# Bee_Hive_MainBoard_V3.net
KiCad netlist of a schematic drawn in Altium Designer
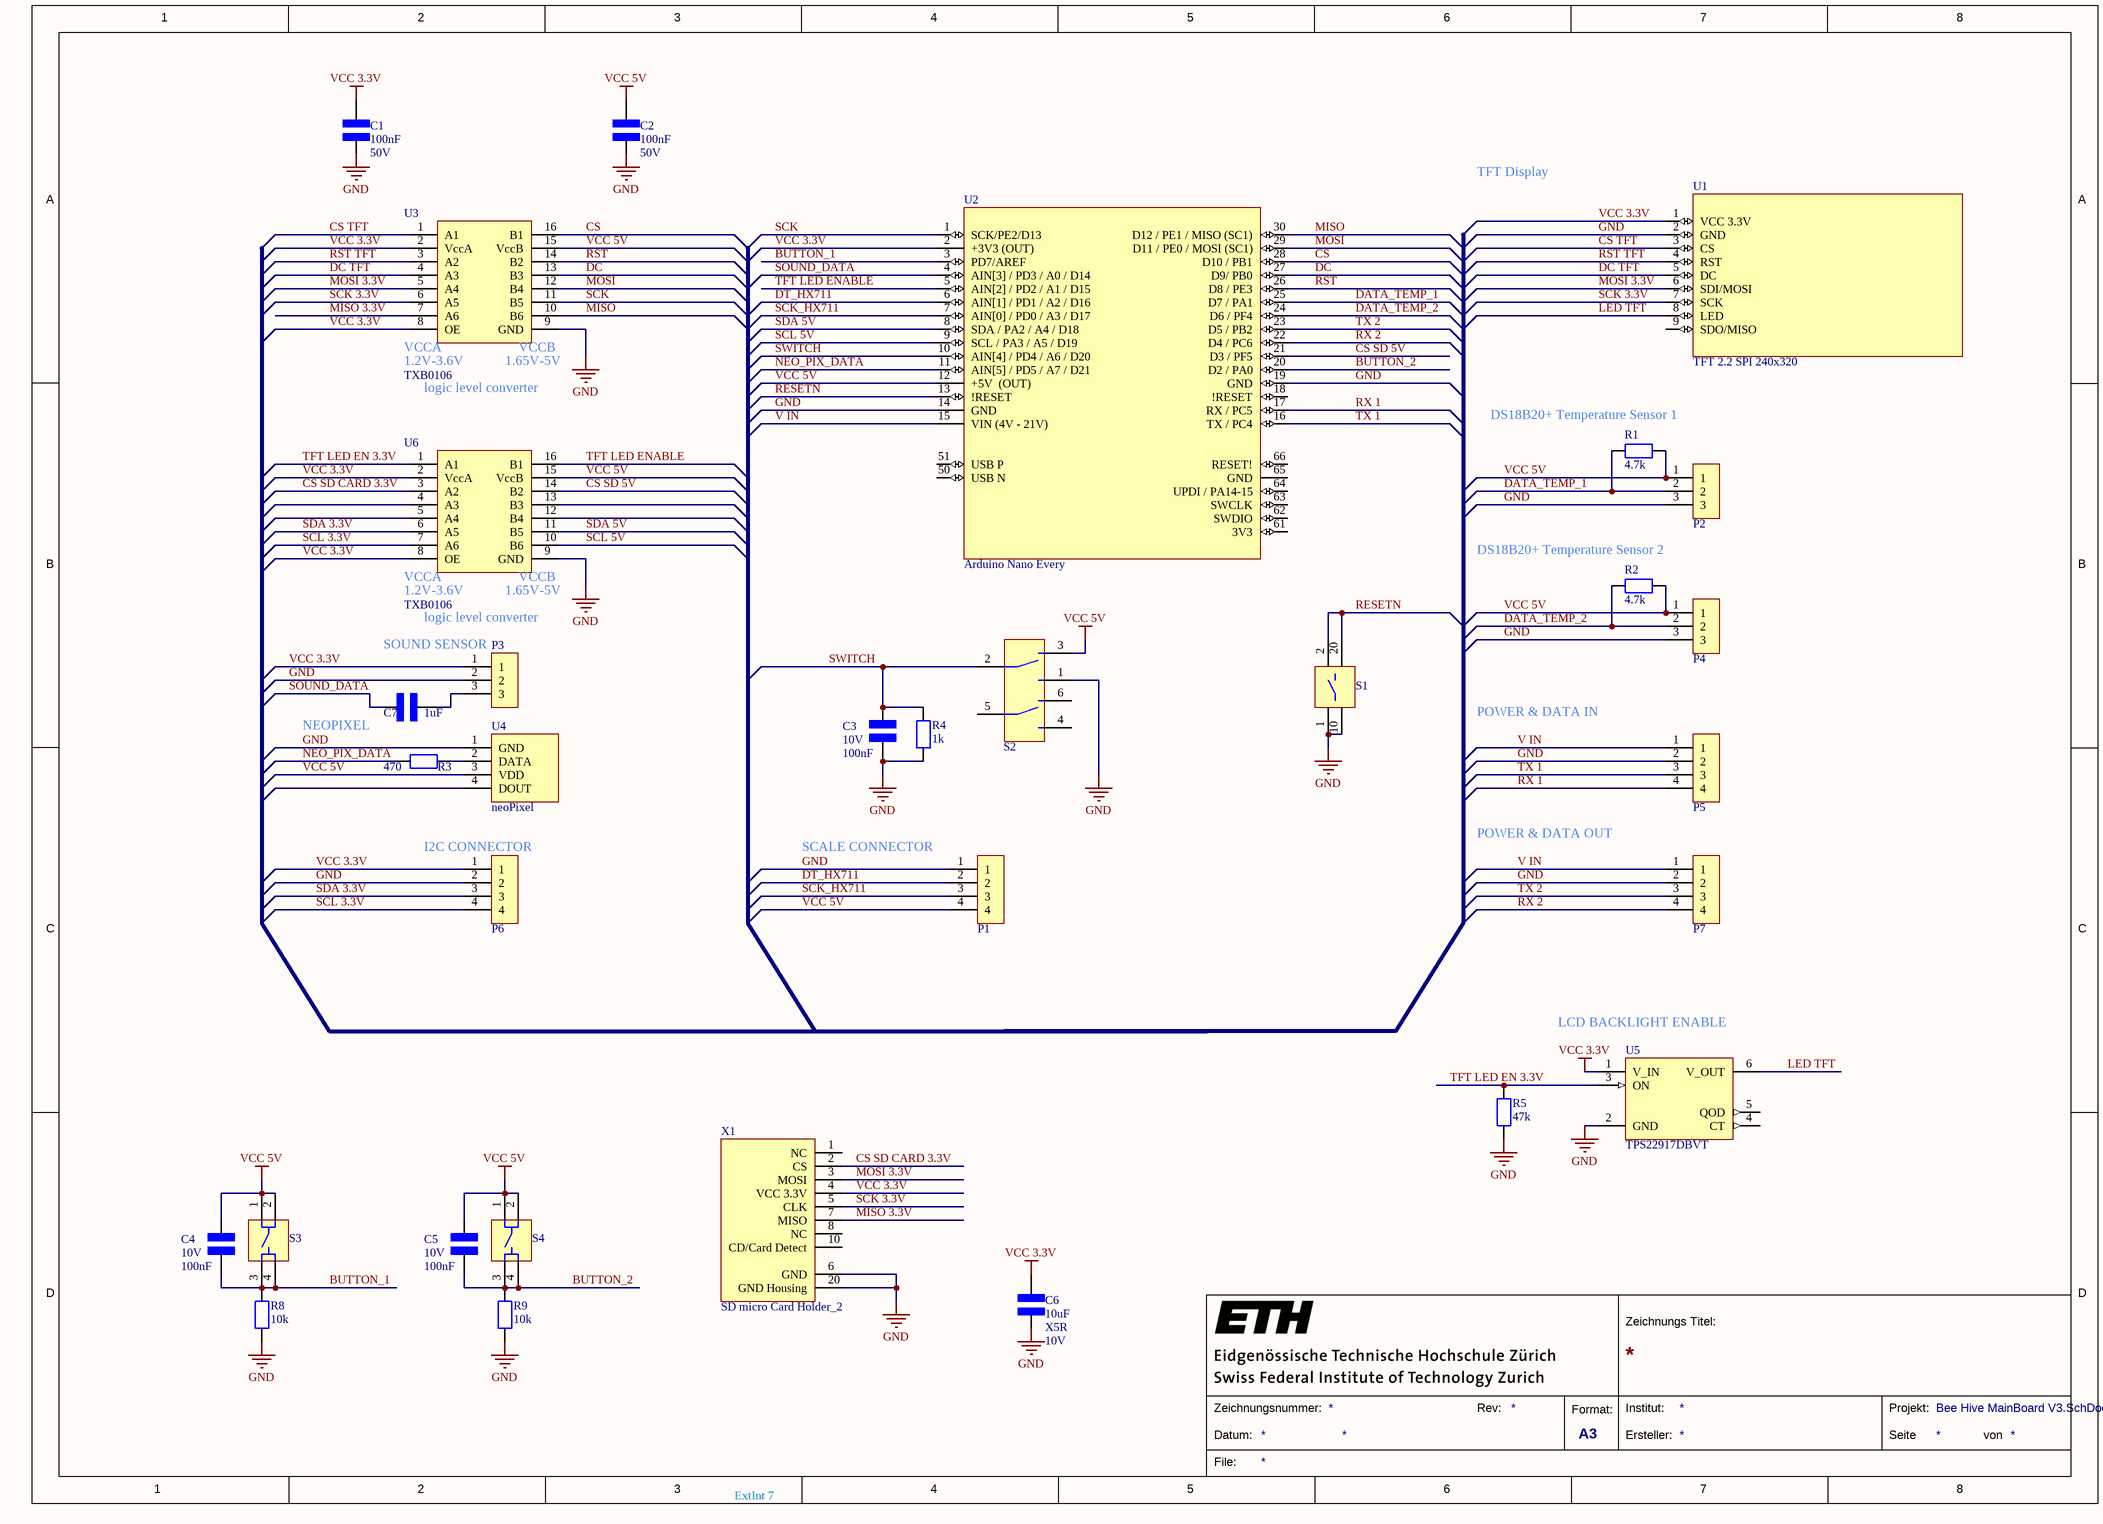
[diagram p0: Bee Hive MainBoard V3.SchDoc]

(export (version "E")
  (design (tool "Eeschema 10.0.6"))
  (components
    (comp (ref "C1")
      (value "100nF")
      (footprint "CAP 0603")
      (description "C CERAMIC SMD")
      (fields (field (name "UMAX") "50V") (field (name "Comment") "100nF 0603_1"))
      (libsource (lib "Library CAP") (part "100nF 0603_1"))
    )
    (comp (ref "C2")
      (value "100nF")
      (footprint "CAP 0603")
      (description "C CERAMIC SMD")
      (fields (field (name "UMAX") "50V") (field (name "Comment") "100nF 0603_1"))
      (libsource (lib "Library CAP") (part "100nF 0603_1"))
    )
    (comp (ref "C3")
      (value "100nF")
      (footprint "CAP 0603")
      (description "C CERAMIC SMD")
      (fields (field (name "UMAX") "10V") (field (name "Comment") "100nF 0603"))
      (libsource (lib "Library CAP") (part "100nF 0603"))
    )
    (comp (ref "C4")
      (value "100nF")
      (footprint "CAP 0603")
      (description "C CERAMIC SMD")
      (fields (field (name "UMAX") "10V") (field (name "Comment") "100nF 0603"))
      (libsource (lib "Library CAP") (part "100nF 0603"))
    )
    (comp (ref "C5")
      (value "100nF")
      (footprint "CAP 0603")
      (description "C CERAMIC SMD")
      (fields (field (name "UMAX") "10V") (field (name "Comment") "100nF 0603"))
      (libsource (lib "Library CAP") (part "100nF 0603"))
    )
    (comp (ref "C6")
      (value "10uF")
      (footprint "CAP 0603")
      (description "C CERAMIC SMD")
      (fields
        (field (name "DIELEKTRIKUM") "X5R")
        (field (name "UMAX") "10V")
        (field (name "Comment") "10uF 0603")
      )
      (libsource (lib "Library CAP") (part "10uF 0603"))
    )
    (comp (ref "C7")
      (value "1uF")
      (footprint "CAP 0805")
      (description "C CERAMIC SMD")
      (fields (field (name "Comment") "100nF 0805"))
      (libsource (lib "Library CAP") (part "100nF 0805"))
    )
    (comp (ref "P1")
      (value "4-Pin Right Angle Housing")
      (footprint "4PIN - RND 205-EK254-2.54-04P")
      (description "4-Pin")
      (libsource (lib "Library Scematic") (part "4-Pin Screw Terminal"))
    )
    (comp (ref "P2")
      (value "3-Pin Right Angle Housing")
      (footprint "3PIN - RND 205-EK254-2.54-03P")
      (description "3-Pin")
      (libsource (lib "Library Scematic") (part "3-Pin Screw Terminal"))
    )
    (comp (ref "P3")
      (value "3-Pin Right Angle Housing")
      (footprint "3PIN - RND 205-EK254-2.54-03P")
      (description "3-Pin")
      (libsource (lib "Library Scematic") (part "3-Pin Screw Terminal"))
    )
    (comp (ref "P4")
      (value "3-Pin Right Angle Housing")
      (footprint "3PIN - RND 205-EK254-2.54-03P")
      (description "3-Pin")
      (libsource (lib "Library Scematic") (part "3-Pin Screw Terminal"))
    )
    (comp (ref "P5")
      (value "4-Pin Right Angle Housing")
      (footprint "4PIN - RND 205-EK254-2.54-04P")
      (description "4-Pin")
      (libsource (lib "Library Scematic") (part "4-Pin Screw Terminal"))
    )
    (comp (ref "P6")
      (value "4-Pin Right Angle Housing")
      (footprint "4PIN - RND 205-EK254-2.54-04P")
      (description "4-Pin")
      (libsource (lib "Library Scematic") (part "4-Pin Screw Terminal"))
    )
    (comp (ref "P7")
      (value "4-Pin Right Angle Housing")
      (footprint "4PIN - RND 205-EK254-2.54-04P")
      (description "4-Pin")
      (libsource (lib "Library Scematic") (part "4-Pin Screw Terminal"))
    )
    (comp (ref "R1")
      (value "4.7k")
      (footprint "RES 0603 FOOTPRINT")
      (description "R SMD")
      (fields (field (name "Comment") "4.7k Ohm 0603"))
      (libsource (lib "Library RES") (part "4.7k Ohm 0603"))
    )
    (comp (ref "R2")
      (value "4.7k")
      (footprint "RES 0603 FOOTPRINT")
      (description "R SMD")
      (fields (field (name "Comment") "4.7k Ohm 0603"))
      (libsource (lib "Library RES") (part "4.7k Ohm 0603"))
    )
    (comp (ref "R3")
      (value "470")
      (footprint "RES 0603 FOOTPRINT")
      (description "R SMD")
      (fields (field (name "Comment") "470 Ohm 0603"))
      (libsource (lib "Library RES") (part "470 Ohm 0603"))
    )
    (comp (ref "R4")
      (value "1k")
      (footprint "RES 0603 FOOTPRINT")
      (description "R SMD")
      (fields (field (name "Comment") "1k Ohm 0603"))
      (libsource (lib "Library RES") (part "1k Ohm 0603"))
    )
    (comp (ref "R5")
      (value "47k")
      (footprint "RES 0603 FOOTPRINT")
      (description "R SMD")
      (fields (field (name "Comment") "47k Ohm 0603"))
      (libsource (lib "Library RES") (part "47k Ohm 0603"))
    )
    (comp (ref "R8")
      (value "10k")
      (footprint "RES 0603 FOOTPRINT")
      (description "R SMD")
      (fields (field (name "Comment") "10k Ohm 0603"))
      (libsource (lib "Library RES") (part "10k Ohm 0603"))
    )
    (comp (ref "R9")
      (value "10k")
      (footprint "RES 0603 FOOTPRINT")
      (description "R SMD")
      (fields (field (name "Comment") "10k Ohm 0603"))
      (libsource (lib "Library RES") (part "10k Ohm 0603"))
    )
    (comp (ref "S1")
      (value "Taster Print_SMD_2")
      (footprint "Taster Print - SMD - KMR241G LFS")
      (description "Taster")
      (libsource (lib "Library Scematic") (part "Taster Print_SMD_2"))
    )
    (comp (ref "S2")
      (value "Schiebeschalter EG2207")
      (footprint "Schiebeschalter on-on 2 P, EG2207")
      (description "Schiebeschalter on-on PCM12SMTR")
      (libsource (lib "Library Scematic") (part "Schiebeschalter EG2207"))
    )
    (comp (ref "S3")
      (value "Taster Print_SMD_3")
      (footprint "Taster Print - SMD - PTS647SM70SMTR2LFS")
      (description "Taster")
      (libsource (lib "Library Scematic") (part "Taster Print_SMD_6"))
    )
    (comp (ref "S4")
      (value "Taster Print_SMD_3")
      (footprint "Taster Print - SMD - PTS647SM70SMTR2LFS")
      (description "Taster")
      (libsource (lib "Library Scematic") (part "Taster Print_SMD_6"))
    )
    (comp (ref "U1")
      (value "TFT 2.2 SPI 240x320")
      (footprint "TFT 2.2 SPI 240x320")
      (libsource (lib "Library Scematic") (part "TFT 2.2 SPI 240x320"))
    )
    (comp (ref "U2")
      (value "Arduino Nano Every")
      (footprint "Arduino Nano Every")
      (description "https://store.arduino.cc/nano-every-pack")
      (libsource (lib "Library Scematic") (part "Arduino Nano Every"))
    )
    (comp (ref "U3")
      (value "TXB0106")
      (footprint "TSSOP-16L")
      (description "Level Converter TXB0106")
      (libsource (lib "Library Scematic") (part "TXB0106 Level Converter"))
    )
    (comp (ref "U4")
      (value "neoPixel")
      (footprint "neoPixel 5050 adafruit 1655")
      (description "neoPixel 5050 adafruit 1655")
      (libsource (lib "Library Scematic") (part "neoPixel 5050 adafruit 1655"))
    )
    (comp (ref "U5")
      (value "TPS22917DBVT")
      (footprint "SOT23 - 6")
      (description "High Side Switch")
      (libsource (lib "Library Scematic") (part "TPS22917DBVT"))
    )
    (comp (ref "U6")
      (value "TXB0106")
      (footprint "TSSOP-16L")
      (description "Level Converter TXB0106")
      (libsource (lib "Library Scematic") (part "TXB0106 Level Converter"))
    )
    (comp (ref "X1")
      (value "SD micro Card Holder_2")
      (footprint "SD Card Holder - micro - 2 - sd Card inserted")
      (description "SD micro Card  Holder")
      (libsource (lib "Library Scematic") (part "SD micro Card Holder_2"))
    )
  )
  (nets
    (net (code "1") (name "/BUTTON_1") (class "Default")
      (node (ref "C4") (pin "2") (pinfunction "2_2") (pintype "passive"))
      (node (ref "R8") (pin "2") (pinfunction "2_2") (pintype "passive"))
      (node (ref "S3") (pin "3") (pinfunction "3_3") (pintype "passive"))
      (node (ref "S3") (pin "4") (pinfunction "4_4") (pintype "passive"))
      (node (ref "U2") (pin "3") (pinfunction "PD7/AREF_3") (pintype "bidirectional"))
    )
    (net (code "2") (name "/BUTTON_2") (class "Default")
      (node (ref "C5") (pin "2") (pinfunction "2_2") (pintype "passive"))
      (node (ref "R9") (pin "2") (pinfunction "2_2") (pintype "passive"))
      (node (ref "S4") (pin "3") (pinfunction "3_3") (pintype "passive"))
      (node (ref "S4") (pin "4") (pinfunction "4_4") (pintype "passive"))
      (node (ref "U2") (pin "20") (pinfunction "D2_/_PA0_20") (pintype "bidirectional"))
    )
    (net (code "3") (name "/CS") (class "Default")
      (node (ref "U2") (pin "28") (pinfunction "D10_/_PB1_28") (pintype "bidirectional"))
      (node (ref "U3") (pin "16") (pinfunction "B1_16") (pintype "passive"))
    )
    (net (code "4") (name "/CS SD 5V") (class "Default")
      (node (ref "U2") (pin "21") (pinfunction "D3_/_PF5_21") (pintype "bidirectional"))
      (node (ref "U6") (pin "14") (pinfunction "B2_14") (pintype "passive"))
    )
    (net (code "5") (name "/CS SD CARD 3.3V") (class "Default")
      (node (ref "U6") (pin "3") (pinfunction "A2_3") (pintype "passive"))
      (node (ref "X1") (pin "2") (pinfunction "CS_2") (pintype "passive"))
    )
    (net (code "6") (name "/CS TFT") (class "Default")
      (node (ref "U1") (pin "3") (pinfunction "CS_3") (pintype "bidirectional"))
      (node (ref "U3") (pin "1") (pinfunction "A1_1") (pintype "power_in"))
    )
    (net (code "7") (name "/DATA_TEMP_1") (class "Default")
      (node (ref "P2") (pin "2") (pinfunction "2_2") (pintype "passive"))
      (node (ref "R1") (pin "2") (pinfunction "2_2") (pintype "passive"))
      (node (ref "U2") (pin "25") (pinfunction "D7_/_PA1_25") (pintype "bidirectional"))
    )
    (net (code "8") (name "/DATA_TEMP_2") (class "Default")
      (node (ref "P4") (pin "2") (pinfunction "2_2") (pintype "passive"))
      (node (ref "R2") (pin "2") (pinfunction "2_2") (pintype "passive"))
      (node (ref "U2") (pin "24") (pinfunction "D6_/_PF4_24") (pintype "bidirectional"))
    )
    (net (code "9") (name "/DC") (class "Default")
      (node (ref "U2") (pin "27") (pinfunction "D9/_PB0_27") (pintype "bidirectional"))
      (node (ref "U3") (pin "13") (pinfunction "B3_13") (pintype "passive"))
    )
    (net (code "10") (name "/DC TFT") (class "Default")
      (node (ref "U1") (pin "5") (pinfunction "DC_5") (pintype "bidirectional"))
      (node (ref "U3") (pin "4") (pinfunction "A3_4") (pintype "passive"))
    )
    (net (code "11") (name "/DT_HX711") (class "Default")
      (node (ref "P1") (pin "2") (pinfunction "2_2") (pintype "passive"))
      (node (ref "U2") (pin "6") (pinfunction "AIN[1]_/_PD1_/_A2_/_D16_6") (pintype "bidirectional"))
    )
    (net (code "12") (name "/LED TFT") (class "Default")
      (node (ref "U1") (pin "8") (pinfunction "LED_8") (pintype "bidirectional"))
      (node (ref "U5") (pin "6") (pinfunction "V_OUT_6") (pintype "power_in"))
    )
    (net (code "13") (name "/MISO") (class "Default")
      (node (ref "U2") (pin "30") (pinfunction "D12_/_PE1_/_MISO_(SC1)_30") (pintype "bidirectional"))
      (node (ref "U3") (pin "10") (pinfunction "B6_10") (pintype "passive"))
    )
    (net (code "14") (name "/MISO 3.3V") (class "Default")
      (node (ref "U3") (pin "7") (pinfunction "A6_7") (pintype "passive"))
      (node (ref "X1") (pin "7") (pinfunction "MISO_7") (pintype "passive"))
    )
    (net (code "15") (name "/MOSI") (class "Default")
      (node (ref "U2") (pin "29") (pinfunction "D11_/_PE0_/_MOSI_(SC1)_29") (pintype "bidirectional"))
      (node (ref "U3") (pin "12") (pinfunction "B4_12") (pintype "passive"))
    )
    (net (code "16") (name "/MOSI 3.3V") (class "Default")
      (node (ref "U1") (pin "6") (pinfunction "SDI/MOSI_6") (pintype "bidirectional"))
      (node (ref "U3") (pin "5") (pinfunction "A4_5") (pintype "passive"))
      (node (ref "X1") (pin "3") (pinfunction "MOSI_3") (pintype "passive"))
    )
    (net (code "17") (name "/NEO_PIX_DATA") (class "Default")
      (node (ref "R3") (pin "1") (pinfunction "1_1") (pintype "passive"))
      (node (ref "U2") (pin "11") (pinfunction "AIN[5]_/_PD5_/_A7_/_D21_11") (pintype "bidirectional"))
    )
    (net (code "18") (name "/RESETN") (class "Default")
      (node (ref "S1") (pin "2") (pinfunction "2_2") (pintype "passive"))
      (node (ref "S1") (pin "20") (pinfunction "20_20") (pintype "passive"))
      (node (ref "U2") (pin "13") (pinfunction "!RESET_13") (pintype "bidirectional"))
    )
    (net (code "19") (name "/RST") (class "Default")
      (node (ref "U2") (pin "26") (pinfunction "D8_/_PE3_26") (pintype "bidirectional"))
      (node (ref "U3") (pin "14") (pinfunction "B2_14") (pintype "passive"))
    )
    (net (code "20") (name "/RST TFT") (class "Default")
      (node (ref "U1") (pin "4") (pinfunction "RST_4") (pintype "bidirectional"))
      (node (ref "U3") (pin "3") (pinfunction "A2_3") (pintype "passive"))
    )
    (net (code "21") (name "/RX 1") (class "Default")
      (node (ref "P5") (pin "4") (pinfunction "4_4") (pintype "passive"))
      (node (ref "U2") (pin "17") (pinfunction "RX_/_PC5_17") (pintype "bidirectional"))
    )
    (net (code "22") (name "/RX 2") (class "Default")
      (node (ref "P7") (pin "4") (pinfunction "4_4") (pintype "passive"))
      (node (ref "U2") (pin "22") (pinfunction "D4_/_PC6_22") (pintype "bidirectional"))
    )
    (net (code "23") (name "/SCK") (class "Default")
      (node (ref "U2") (pin "1") (pinfunction "SCK/PE2/D13_1") (pintype "bidirectional"))
      (node (ref "U3") (pin "11") (pinfunction "B5_11") (pintype "passive"))
    )
    (net (code "24") (name "/SCK 3.3V") (class "Default")
      (node (ref "U1") (pin "7") (pinfunction "SCK_7") (pintype "bidirectional"))
      (node (ref "U3") (pin "6") (pinfunction "A5_6") (pintype "passive"))
      (node (ref "X1") (pin "5") (pinfunction "CLK_5") (pintype "passive"))
    )
    (net (code "25") (name "/SCK_HX711") (class "Default")
      (node (ref "P1") (pin "3") (pinfunction "3_3") (pintype "passive"))
      (node (ref "U2") (pin "7") (pinfunction "AIN[0]_/_PD0_/_A3_/_D17_7") (pintype "bidirectional"))
    )
    (net (code "26") (name "/SCL 3.3V") (class "Default")
      (node (ref "P6") (pin "4") (pinfunction "4_4") (pintype "passive"))
      (node (ref "U6") (pin "7") (pinfunction "A6_7") (pintype "passive"))
    )
    (net (code "27") (name "/SCL 5V") (class "Default")
      (node (ref "U2") (pin "9") (pinfunction "SCL_/_PA3_/_A5_/_D19_9") (pintype "bidirectional"))
      (node (ref "U6") (pin "10") (pinfunction "B6_10") (pintype "passive"))
    )
    (net (code "28") (name "/SDA 3.3V") (class "Default")
      (node (ref "P6") (pin "3") (pinfunction "3_3") (pintype "passive"))
      (node (ref "U6") (pin "6") (pinfunction "A5_6") (pintype "passive"))
    )
    (net (code "29") (name "/SDA 5V") (class "Default")
      (node (ref "U2") (pin "8") (pinfunction "SDA_/_PA2_/_A4_/_D18_8") (pintype "bidirectional"))
      (node (ref "U6") (pin "11") (pinfunction "B5_11") (pintype "passive"))
    )
    (net (code "30") (name "/SOUND_DATA") (class "Default")
      (node (ref "C7") (pin "1") (pinfunction "1_1") (pintype "passive"))
      (node (ref "U2") (pin "4") (pinfunction "AIN[3]_/_PD3_/_A0_/_D14_4") (pintype "bidirectional"))
    )
    (net (code "31") (name "/SWITCH") (class "Default")
      (node (ref "C3") (pin "1") (pinfunction "1_1") (pintype "passive"))
      (node (ref "R4") (pin "2") (pinfunction "2_2") (pintype "passive"))
      (node (ref "S2") (pin "2") (pinfunction "2_2") (pintype "passive"))
      (node (ref "U2") (pin "10") (pinfunction "AIN[4]_/_PD4_/_A6_/_D20_10") (pintype "bidirectional"))
    )
    (net (code "32") (name "/TFT LED EN 3.3V") (class "Default")
      (node (ref "R5") (pin "2") (pinfunction "2_2") (pintype "passive"))
      (node (ref "U5") (pin "3") (pinfunction "ON_3") (pintype "input"))
      (node (ref "U6") (pin "1") (pinfunction "A1_1") (pintype "power_in"))
    )
    (net (code "33") (name "/TFT LED ENABLE") (class "Default")
      (node (ref "U2") (pin "5") (pinfunction "AIN[2]_/_PD2_/_A1_/_D15_5") (pintype "bidirectional"))
      (node (ref "U6") (pin "16") (pinfunction "B1_16") (pintype "passive"))
    )
    (net (code "34") (name "/TX 1") (class "Default")
      (node (ref "P5") (pin "3") (pinfunction "3_3") (pintype "passive"))
      (node (ref "U2") (pin "16") (pinfunction "TX_/_PC4_16") (pintype "bidirectional"))
    )
    (net (code "35") (name "/TX 2") (class "Default")
      (node (ref "P7") (pin "3") (pinfunction "3_3") (pintype "passive"))
      (node (ref "U2") (pin "23") (pinfunction "D5_/_PB2_23") (pintype "bidirectional"))
    )
    (net (code "36") (name "/V IN") (class "Default")
      (node (ref "P5") (pin "1") (pinfunction "1_1") (pintype "passive"))
      (node (ref "P7") (pin "1") (pinfunction "1_1") (pintype "passive"))
      (node (ref "U2") (pin "15") (pinfunction "VIN_(4V_-_21V)_15") (pintype "power_in"))
    )
    (net (code "37") (name "GND") (class "Default")
      (node (ref "C1") (pin "1") (pinfunction "1_1") (pintype "passive"))
      (node (ref "C2") (pin "1") (pinfunction "1_1") (pintype "passive"))
      (node (ref "C3") (pin "2") (pinfunction "2_2") (pintype "passive"))
      (node (ref "C6") (pin "1") (pinfunction "1_1") (pintype "passive"))
      (node (ref "P1") (pin "1") (pinfunction "1_1") (pintype "passive"))
      (node (ref "P2") (pin "3") (pinfunction "3_3") (pintype "passive"))
      (node (ref "P3") (pin "2") (pinfunction "2_2") (pintype "passive"))
      (node (ref "P4") (pin "3") (pinfunction "3_3") (pintype "passive"))
      (node (ref "P5") (pin "2") (pinfunction "2_2") (pintype "passive"))
      (node (ref "P6") (pin "2") (pinfunction "2_2") (pintype "passive"))
      (node (ref "P7") (pin "2") (pinfunction "2_2") (pintype "passive"))
      (node (ref "R4") (pin "1") (pinfunction "1_1") (pintype "passive"))
      (node (ref "R5") (pin "1") (pinfunction "1_1") (pintype "passive"))
      (node (ref "R8") (pin "1") (pinfunction "1_1") (pintype "passive"))
      (node (ref "R9") (pin "1") (pinfunction "1_1") (pintype "passive"))
      (node (ref "S1") (pin "1") (pinfunction "1_1") (pintype "passive"))
      (node (ref "S1") (pin "10") (pinfunction "10_10") (pintype "passive"))
      (node (ref "S2") (pin "1") (pinfunction "1_1") (pintype "passive"))
      (node (ref "U1") (pin "2") (pinfunction "GND_2") (pintype "bidirectional"))
      (node (ref "U2") (pin "14") (pinfunction "GND_14") (pintype "power_in"))
      (node (ref "U2") (pin "19") (pinfunction "GND_19") (pintype "bidirectional"))
      (node (ref "U3") (pin "9") (pinfunction "GND_9") (pintype "passive"))
      (node (ref "U4") (pin "1") (pinfunction "GND_1") (pintype "passive"))
      (node (ref "U5") (pin "2") (pinfunction "GND_2") (pintype "power_in"))
      (node (ref "U6") (pin "9") (pinfunction "GND_9") (pintype "passive"))
      (node (ref "X1") (pin "20") (pinfunction "GND_Housing_20") (pintype "passive"))
      (node (ref "X1") (pin "6") (pinfunction "GND_6") (pintype "passive"))
    )
    (net (code "38") (name "Net-(C7-Pad2)") (class "Default")
      (node (ref "C7") (pin "2") (pinfunction "2_2") (pintype "passive"))
      (node (ref "P3") (pin "3") (pinfunction "3_3") (pintype "passive"))
    )
    (net (code "39") (name "Net-(U4-DATA)") (class "Default")
      (node (ref "R3") (pin "2") (pinfunction "2_2") (pintype "passive"))
      (node (ref "U4") (pin "2") (pinfunction "DATA_2") (pintype "passive"))
    )
    (net (code "40") (name "VCC 3.3V") (class "Default")
      (node (ref "C1") (pin "2") (pinfunction "2_2") (pintype "passive"))
      (node (ref "C6") (pin "2") (pinfunction "2_2") (pintype "passive"))
      (node (ref "P3") (pin "1") (pinfunction "1_1") (pintype "passive"))
      (node (ref "P6") (pin "1") (pinfunction "1_1") (pintype "passive"))
      (node (ref "U1") (pin "1") (pinfunction "VCC_3.3V_1") (pintype "bidirectional"))
      (node (ref "U2") (pin "2") (pinfunction "+3V3_(OUT)_2") (pintype "power_in"))
      (node (ref "U3") (pin "2") (pinfunction "VccA_2") (pintype "passive"))
      (node (ref "U3") (pin "8") (pinfunction "OE_8") (pintype "passive"))
      (node (ref "U5") (pin "1") (pinfunction "V_IN_1") (pintype "power_in"))
      (node (ref "U6") (pin "2") (pinfunction "VccA_2") (pintype "passive"))
      (node (ref "U6") (pin "8") (pinfunction "OE_8") (pintype "passive"))
      (node (ref "X1") (pin "4") (pinfunction "VCC_3.3V_4") (pintype "passive"))
    )
    (net (code "41") (name "VCC 5V") (class "Default")
      (node (ref "C2") (pin "2") (pinfunction "2_2") (pintype "passive"))
      (node (ref "C4") (pin "1") (pinfunction "1_1") (pintype "passive"))
      (node (ref "C5") (pin "1") (pinfunction "1_1") (pintype "passive"))
      (node (ref "P1") (pin "4") (pinfunction "4_4") (pintype "passive"))
      (node (ref "P2") (pin "1") (pinfunction "1_1") (pintype "passive"))
      (node (ref "P4") (pin "1") (pinfunction "1_1") (pintype "passive"))
      (node (ref "R1") (pin "1") (pinfunction "1_1") (pintype "passive"))
      (node (ref "R2") (pin "1") (pinfunction "1_1") (pintype "passive"))
      (node (ref "S2") (pin "3") (pinfunction "3_3") (pintype "passive"))
      (node (ref "S3") (pin "1") (pinfunction "1_1") (pintype "passive"))
      (node (ref "S3") (pin "2") (pinfunction "2_2") (pintype "passive"))
      (node (ref "S4") (pin "1") (pinfunction "1_1") (pintype "passive"))
      (node (ref "S4") (pin "2") (pinfunction "2_2") (pintype "passive"))
      (node (ref "U2") (pin "12") (pinfunction "+5V__(OUT)_12") (pintype "power_in"))
      (node (ref "U3") (pin "15") (pinfunction "VccB_15") (pintype "passive"))
      (node (ref "U4") (pin "3") (pinfunction "VDD_3") (pintype "passive"))
      (node (ref "U6") (pin "15") (pinfunction "VccB_15") (pintype "passive"))
    )
    (net (code "42") (name "unconnected-(S2-Pad4)") (class "Default")
      (node (ref "S2") (pin "4") (pinfunction "4_4") (pintype "passive"))
    )
    (net (code "43") (name "unconnected-(S2-Pad5)") (class "Default")
      (node (ref "S2") (pin "5") (pinfunction "5_5") (pintype "passive"))
    )
    (net (code "44") (name "unconnected-(S2-Pad6)") (class "Default")
      (node (ref "S2") (pin "6") (pinfunction "6_6") (pintype "passive"))
    )
    (net (code "45") (name "unconnected-(U1-SDO{slash}MISO-Pad9)") (class "Default")
      (node (ref "U1") (pin "9") (pinfunction "SDO/MISO_9") (pintype "bidirectional"))
    )
    (net (code "46") (name "unconnected-(U2-!RESET-Pad18)") (class "Default")
      (node (ref "U2") (pin "18") (pinfunction "!RESET_18") (pintype "bidirectional"))
    )
    (net (code "47") (name "unconnected-(U2-3V3-Pad61)") (class "Default")
      (node (ref "U2") (pin "61") (pinfunction "3V3_61") (pintype "bidirectional"))
    )
    (net (code "48") (name "unconnected-(U2-GND-Pad65)") (class "Default")
      (node (ref "U2") (pin "65") (pinfunction "GND_65") (pintype "power_in"))
    )
    (net (code "49") (name "unconnected-(U2-RESET!-Pad66)") (class "Default")
      (node (ref "U2") (pin "66") (pinfunction "RESET!_66") (pintype "bidirectional"))
    )
    (net (code "50") (name "unconnected-(U2-SWCLK-Pad63)") (class "Default")
      (node (ref "U2") (pin "63") (pinfunction "SWCLK_63") (pintype "bidirectional"))
    )
    (net (code "51") (name "unconnected-(U2-SWDIO-Pad62)") (class "Default")
      (node (ref "U2") (pin "62") (pinfunction "SWDIO_62") (pintype "bidirectional"))
    )
    (net (code "52") (name "unconnected-(U2-UPDI_{slash}_PA14-15-Pad64)") (class "Default")
      (node (ref "U2") (pin "64") (pinfunction "UPDI_/_PA14-15_64") (pintype "bidirectional"))
    )
    (net (code "53") (name "unconnected-(U2-USB_N-Pad50)") (class "Default")
      (node (ref "U2") (pin "50") (pinfunction "USB_N_50") (pintype "bidirectional"))
    )
    (net (code "54") (name "unconnected-(U2-USB_P-Pad51)") (class "Default")
      (node (ref "U2") (pin "51") (pinfunction "USB_P_51") (pintype "bidirectional"))
    )
    (net (code "55") (name "unconnected-(U4-DOUT-Pad4)") (class "Default")
      (node (ref "U4") (pin "4") (pinfunction "DOUT_4") (pintype "passive"))
    )
    (net (code "56") (name "unconnected-(U5-CT-Pad4)") (class "Default")
      (node (ref "U5") (pin "4") (pinfunction "CT_4") (pintype "output"))
    )
    (net (code "57") (name "unconnected-(U5-QOD-Pad5)") (class "Default")
      (node (ref "U5") (pin "5") (pinfunction "QOD_5") (pintype "output"))
    )
    (net (code "58") (name "unconnected-(U6-A3-Pad4)") (class "Default")
      (node (ref "U6") (pin "4") (pinfunction "A3_4") (pintype "passive"))
    )
    (net (code "59") (name "unconnected-(U6-A4-Pad5)") (class "Default")
      (node (ref "U6") (pin "5") (pinfunction "A4_5") (pintype "passive"))
    )
    (net (code "60") (name "unconnected-(U6-B3-Pad13)") (class "Default")
      (node (ref "U6") (pin "13") (pinfunction "B3_13") (pintype "passive"))
    )
    (net (code "61") (name "unconnected-(U6-B4-Pad12)") (class "Default")
      (node (ref "U6") (pin "12") (pinfunction "B4_12") (pintype "passive"))
    )
    (net (code "62") (name "unconnected-(X1-CD{slash}Card_Detect-Pad10)") (class "Default")
      (node (ref "X1") (pin "10") (pinfunction "CD/Card_Detect_10") (pintype "passive"))
    )
    (net (code "63") (name "unconnected-(X1-NC-Pad1)") (class "Default")
      (node (ref "X1") (pin "1") (pinfunction "NC_1") (pintype "passive"))
    )
    (net (code "64") (name "unconnected-(X1-NC-Pad8)") (class "Default")
      (node (ref "X1") (pin "8") (pinfunction "NC_8") (pintype "passive"))
    )
  )
)
